# XBee-Regulated-v14.net
KiCad netlist of a schematic drawn in EAGLE
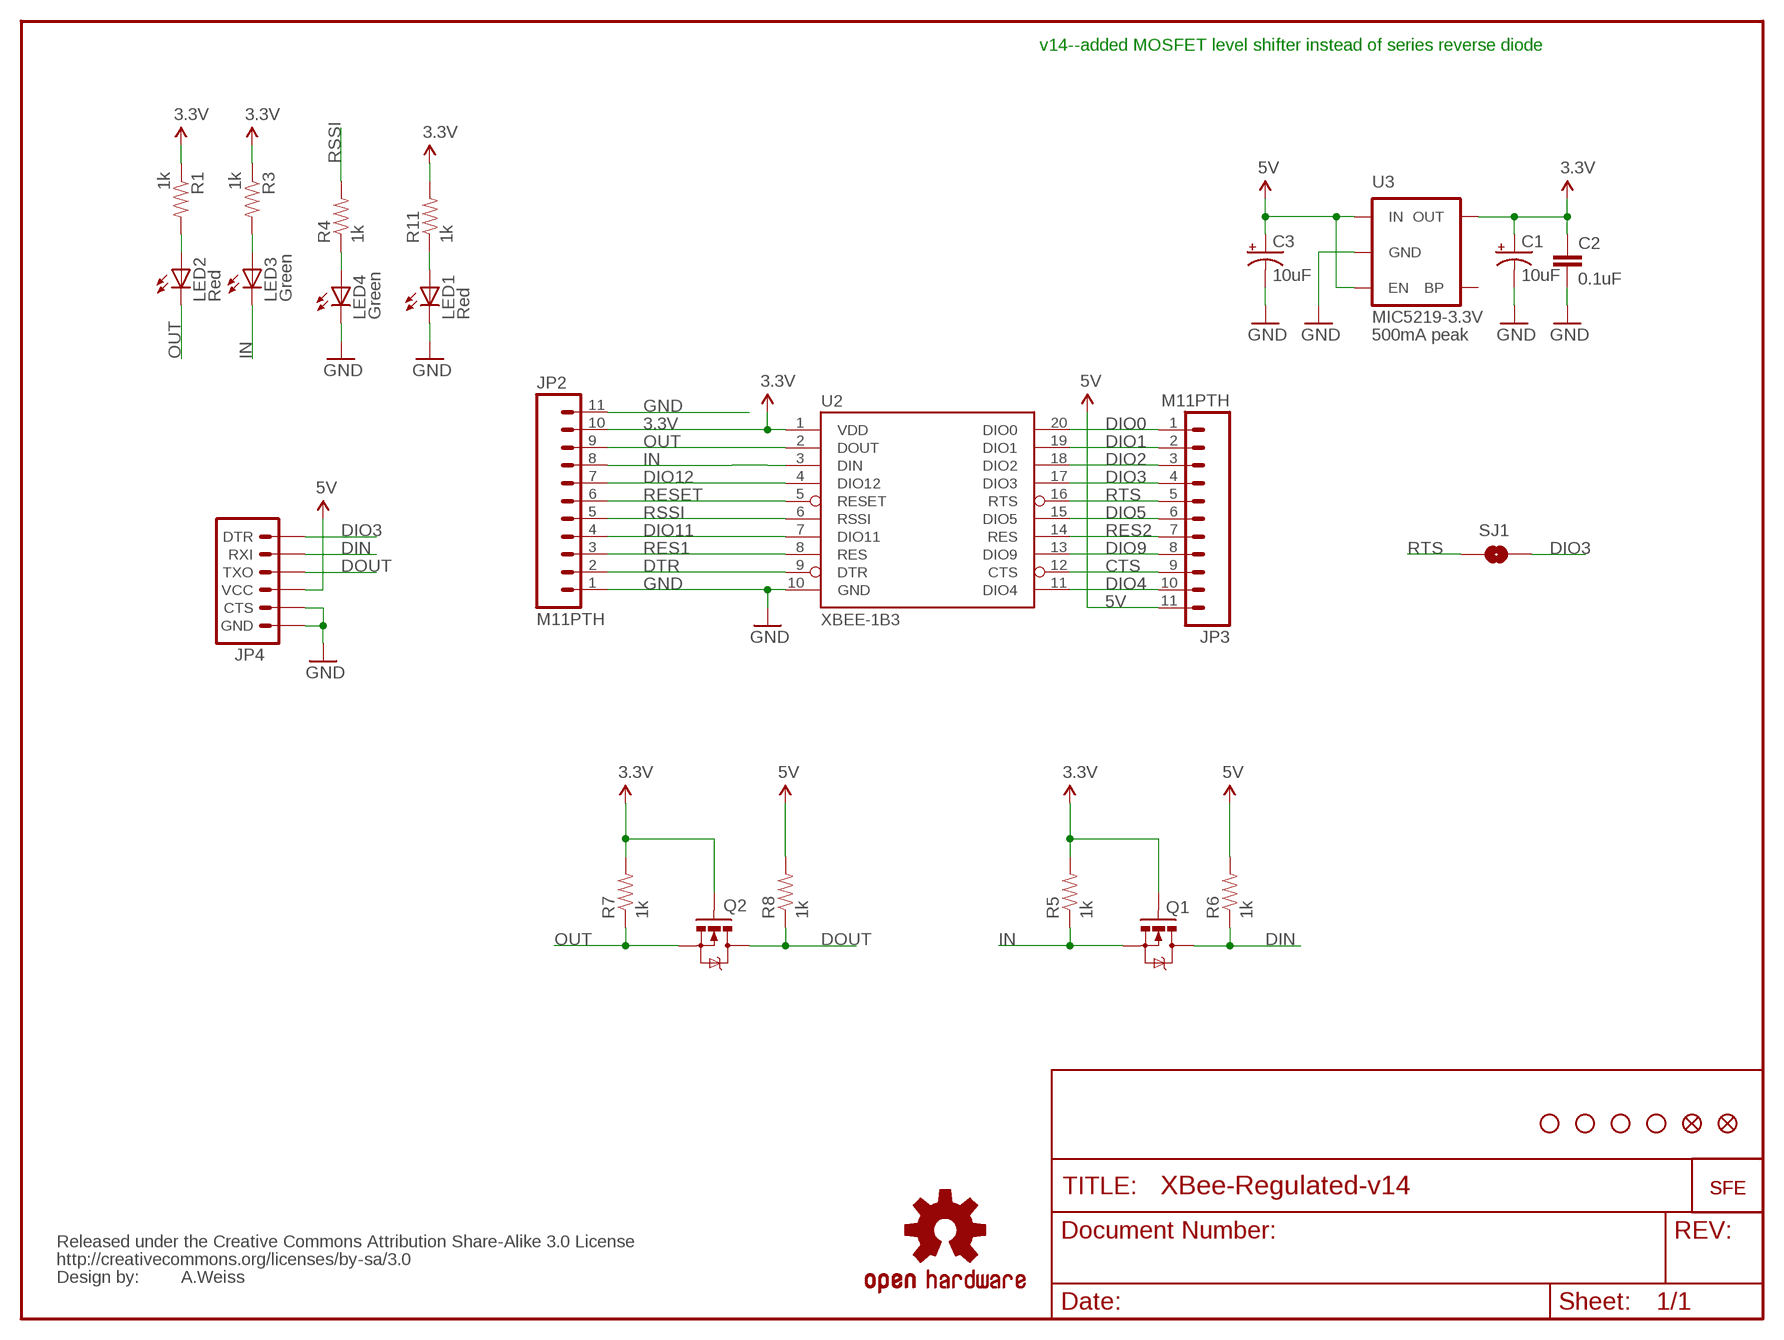
[diagram p0: schematic, sheet 1]

(export (version "E")
  (design (tool "Eeschema 10.0.6"))
  (components
    (comp (ref "C1")
      (value "10uF")
      (footprint "eagle-import:EIA3216")
      (libsource (lib "eagle-import") (part "CAP_POL1206"))
    )
    (comp (ref "C2")
      (value "0.1uF")
      (footprint "eagle-import:0402-CAP")
      (libsource (lib "eagle-import") (part "CAP0402-CAP"))
    )
    (comp (ref "C3")
      (value "10uF")
      (footprint "eagle-import:EIA3216")
      (libsource (lib "eagle-import") (part "CAP_POL1206"))
    )
    (comp (ref "JP2")
      (value "M11PTH")
      (footprint "eagle-import:1X11")
      (libsource (lib "eagle-import") (part "M11PTH"))
    )
    (comp (ref "JP3")
      (value "M11PTH")
      (footprint "eagle-import:1X11")
      (libsource (lib "eagle-import") (part "M11PTH"))
    )
    (comp (ref "JP4")
      (value "ARDUINO_SERIAL_PROGRAMPTH")
      (footprint "eagle-import:1X06")
      (libsource (lib "eagle-import") (part "ARDUINO_SERIAL_PROGRAMPTH"))
    )
    (comp (ref "LED1")
      (value "Red")
      (footprint "eagle-import:LED-0603")
      (libsource (lib "eagle-import") (part "LED0603"))
    )
    (comp (ref "LED2")
      (value "Red")
      (footprint "eagle-import:LED-0603")
      (libsource (lib "eagle-import") (part "LED0603"))
    )
    (comp (ref "LED3")
      (value "Green")
      (footprint "eagle-import:LED-0603")
      (libsource (lib "eagle-import") (part "LED0603"))
    )
    (comp (ref "LED4")
      (value "Green")
      (footprint "eagle-import:LED-0603")
      (libsource (lib "eagle-import") (part "LED0603"))
    )
    (comp (ref "Q1")
      (value "MOSFET-NCHANNELSMD")
      (footprint "eagle-import:SOT23-3")
      (libsource (lib "eagle-import") (part "MOSFET-NCHANNELSMD"))
    )
    (comp (ref "Q2")
      (value "MOSFET-NCHANNELSMD")
      (footprint "eagle-import:SOT23-3")
      (libsource (lib "eagle-import") (part "MOSFET-NCHANNELSMD"))
    )
    (comp (ref "R1")
      (value "1k")
      (footprint "eagle-import:0402-RES")
      (libsource (lib "eagle-import") (part "RESISTOR0402-RES"))
    )
    (comp (ref "R3")
      (value "1k")
      (footprint "eagle-import:0402-RES")
      (libsource (lib "eagle-import") (part "RESISTOR0402-RES"))
    )
    (comp (ref "R4")
      (value "1k")
      (footprint "eagle-import:0402-RES")
      (libsource (lib "eagle-import") (part "RESISTOR0402-RES"))
    )
    (comp (ref "R5")
      (value "1k")
      (footprint "eagle-import:0402-RES")
      (libsource (lib "eagle-import") (part "RESISTOR0402-RES"))
    )
    (comp (ref "R6")
      (value "1k")
      (footprint "eagle-import:0402-RES")
      (libsource (lib "eagle-import") (part "RESISTOR0402-RES"))
    )
    (comp (ref "R7")
      (value "1k")
      (footprint "eagle-import:0402-RES")
      (libsource (lib "eagle-import") (part "RESISTOR0402-RES"))
    )
    (comp (ref "R8")
      (value "1k")
      (footprint "eagle-import:0402-RES")
      (libsource (lib "eagle-import") (part "RESISTOR0402-RES"))
    )
    (comp (ref "R11")
      (value "1k")
      (footprint "eagle-import:0402-RES")
      (libsource (lib "eagle-import") (part "RESISTOR0402-RES"))
    )
    (comp (ref "SJ1")
      (value "SOLDERJUMPERNO")
      (footprint "eagle-import:SJ_2S-NO")
      (libsource (lib "eagle-import") (part "SOLDERJUMPERNO"))
    )
    (comp (ref "U$1")
      (value "LOGO-SFESK")
      (footprint "eagle-import:SFE-LOGO-FLAME")
      (libsource (lib "eagle-import") (part "LOGO-SFESK"))
    )
    (comp (ref "U$3")
      (value "OSHW-LOGOS")
      (footprint "eagle-import:OSHW-LOGO-S")
      (libsource (lib "eagle-import") (part "OSHW-LOGOS"))
    )
    (comp (ref "U$4")
      (value "LOGO-SFENEW")
      (footprint "eagle-import:SFE-NEW-WEBLOGO")
      (libsource (lib "eagle-import") (part "LOGO-SFENEW"))
    )
    (comp (ref "U$5")
      (value "STAND-OFF")
      (footprint "eagle-import:STAND-OFF")
      (libsource (lib "eagle-import") (part "STAND-OFF"))
    )
    (comp (ref "U$7")
      (value "FIDUCIAL1X2")
      (footprint "eagle-import:FIDUCIAL-1X2")
      (libsource (lib "eagle-import") (part "FIDUCIAL1X2"))
    )
    (comp (ref "U$8")
      (value "CREATIVE_COMMONS")
      (footprint "eagle-import:CREATIVE_COMMONS")
      (libsource (lib "eagle-import") (part "CREATIVE_COMMONS"))
    )
    (comp (ref "U$9")
      (value "STAND-OFF")
      (footprint "eagle-import:STAND-OFF")
      (libsource (lib "eagle-import") (part "STAND-OFF"))
    )
    (comp (ref "U$10")
      (value "STAND-OFF")
      (footprint "eagle-import:STAND-OFF")
      (libsource (lib "eagle-import") (part "STAND-OFF"))
    )
    (comp (ref "U$11")
      (value "STAND-OFF")
      (footprint "eagle-import:STAND-OFF")
      (libsource (lib "eagle-import") (part "STAND-OFF"))
    )
    (comp (ref "U$16")
      (value "FIDUCIAL1X2")
      (footprint "eagle-import:FIDUCIAL-1X2")
      (libsource (lib "eagle-import") (part "FIDUCIAL1X2"))
    )
    (comp (ref "U2")
      (value "XBEE-1B3")
      (footprint "eagle-import:XBEE-SMD")
      (libsource (lib "eagle-import") (part "XBEE-1B3"))
    )
    (comp (ref "U3")
      (value "V_REG_LDOSMD")
      (footprint "eagle-import:SOT23-5")
      (libsource (lib "eagle-import") (part "V_REG_LDOSMD"))
    )
  )
  (nets
    (net (code "1") (name "/CTS") (class "Default")
      (node (ref "JP3") (pin "9") (pinfunction "9_9") (pintype "passive"))
      (node (ref "U2") (pin "12") (pinfunction "CTS_12") (pintype "output"))
    )
    (net (code "2") (name "/DIN") (class "Default")
      (node (ref "JP4") (pin "2") (pinfunction "RXI_2") (pintype "passive"))
      (node (ref "Q1") (pin "3") (pinfunction "D_3") (pintype "passive"))
      (node (ref "R6") (pin "1") (pinfunction "1_1") (pintype "passive"))
    )
    (net (code "3") (name "/DIO0") (class "Default")
      (node (ref "JP3") (pin "1") (pinfunction "1_1") (pintype "passive"))
      (node (ref "U2") (pin "20") (pinfunction "DIO0_20") (pintype "bidirectional"))
    )
    (net (code "4") (name "/DIO1") (class "Default")
      (node (ref "JP3") (pin "2") (pinfunction "2_2") (pintype "passive"))
      (node (ref "U2") (pin "19") (pinfunction "DIO1_19") (pintype "bidirectional"))
    )
    (net (code "5") (name "/DIO2") (class "Default")
      (node (ref "JP3") (pin "3") (pinfunction "3_3") (pintype "passive"))
      (node (ref "U2") (pin "18") (pinfunction "DIO2_18") (pintype "bidirectional"))
    )
    (net (code "6") (name "/DIO3") (class "Default")
      (node (ref "JP3") (pin "4") (pinfunction "4_4") (pintype "passive"))
      (node (ref "JP4") (pin "1") (pinfunction "DTR_1") (pintype "passive"))
      (node (ref "SJ1") (pin "2") (pinfunction "2_2") (pintype "passive"))
      (node (ref "U2") (pin "17") (pinfunction "DIO3_17") (pintype "bidirectional"))
    )
    (net (code "7") (name "/DIO4") (class "Default")
      (node (ref "JP3") (pin "10") (pinfunction "10_10") (pintype "passive"))
      (node (ref "U2") (pin "11") (pinfunction "DIO4_11") (pintype "bidirectional"))
    )
    (net (code "8") (name "/DIO5") (class "Default")
      (node (ref "JP3") (pin "6") (pinfunction "6_6") (pintype "passive"))
      (node (ref "U2") (pin "15") (pinfunction "DIO5_15") (pintype "bidirectional"))
    )
    (net (code "9") (name "/DIO9") (class "Default")
      (node (ref "JP3") (pin "8") (pinfunction "8_8") (pintype "passive"))
      (node (ref "U2") (pin "13") (pinfunction "DIO9_13") (pintype "bidirectional"))
    )
    (net (code "10") (name "/DIO11") (class "Default")
      (node (ref "JP2") (pin "4") (pinfunction "4_4") (pintype "passive"))
      (node (ref "U2") (pin "7") (pinfunction "DIO11_7") (pintype "bidirectional"))
    )
    (net (code "11") (name "/DIO12") (class "Default")
      (node (ref "JP2") (pin "7") (pinfunction "7_7") (pintype "passive"))
      (node (ref "U2") (pin "4") (pinfunction "DIO12_4") (pintype "bidirectional"))
    )
    (net (code "12") (name "/DOUT") (class "Default")
      (node (ref "JP4") (pin "3") (pinfunction "TXO_3") (pintype "passive"))
      (node (ref "Q2") (pin "3") (pinfunction "D_3") (pintype "passive"))
      (node (ref "R8") (pin "1") (pinfunction "1_1") (pintype "passive"))
    )
    (net (code "13") (name "/DTR") (class "Default")
      (node (ref "JP2") (pin "2") (pinfunction "2_2") (pintype "passive"))
      (node (ref "U2") (pin "9") (pinfunction "DTR_9") (pintype "bidirectional"))
    )
    (net (code "14") (name "/IN") (class "Default")
      (node (ref "JP2") (pin "8") (pinfunction "8_8") (pintype "passive"))
      (node (ref "LED3") (pin "C") (pinfunction "C_C") (pintype "passive"))
      (node (ref "Q1") (pin "2") (pinfunction "S_2") (pintype "passive"))
      (node (ref "R5") (pin "1") (pinfunction "1_1") (pintype "passive"))
      (node (ref "U2") (pin "3") (pinfunction "DIN_3") (pintype "input"))
    )
    (net (code "15") (name "/OUT") (class "Default")
      (node (ref "JP2") (pin "9") (pinfunction "9_9") (pintype "passive"))
      (node (ref "LED2") (pin "C") (pinfunction "C_C") (pintype "passive"))
      (node (ref "Q2") (pin "2") (pinfunction "S_2") (pintype "passive"))
      (node (ref "R7") (pin "1") (pinfunction "1_1") (pintype "passive"))
      (node (ref "U2") (pin "2") (pinfunction "DOUT_2") (pintype "output"))
    )
    (net (code "16") (name "/RES1") (class "Default")
      (node (ref "JP2") (pin "3") (pinfunction "3_3") (pintype "passive"))
      (node (ref "U2") (pin "8") (pinfunction "RES_8") (pintype "bidirectional"))
    )
    (net (code "17") (name "/RES2") (class "Default")
      (node (ref "JP3") (pin "7") (pinfunction "7_7") (pintype "passive"))
      (node (ref "U2") (pin "14") (pinfunction "RES_14") (pintype "bidirectional"))
    )
    (net (code "18") (name "/RESET") (class "Default")
      (node (ref "JP2") (pin "6") (pinfunction "6_6") (pintype "passive"))
      (node (ref "U2") (pin "5") (pinfunction "RESET_5") (pintype "input"))
    )
    (net (code "19") (name "/RSSI") (class "Default")
      (node (ref "JP2") (pin "5") (pinfunction "5_5") (pintype "passive"))
      (node (ref "R4") (pin "2") (pinfunction "2_2") (pintype "passive"))
      (node (ref "U2") (pin "6") (pinfunction "RSSI_6") (pintype "bidirectional"))
    )
    (net (code "20") (name "/RTS") (class "Default")
      (node (ref "JP3") (pin "5") (pinfunction "5_5") (pintype "passive"))
      (node (ref "SJ1") (pin "1") (pinfunction "1_1") (pintype "passive"))
      (node (ref "U2") (pin "16") (pinfunction "RTS_16") (pintype "input"))
    )
    (net (code "21") (name "3.3V") (class "Default")
      (node (ref "C1") (pin "A") (pinfunction "+_A") (pintype "passive"))
      (node (ref "C2") (pin "1") (pinfunction "1_1") (pintype "passive"))
      (node (ref "JP2") (pin "10") (pinfunction "10_10") (pintype "passive"))
      (node (ref "Q1") (pin "1") (pinfunction "G_1") (pintype "passive"))
      (node (ref "Q2") (pin "1") (pinfunction "G_1") (pintype "passive"))
      (node (ref "R1") (pin "1") (pinfunction "1_1") (pintype "passive"))
      (node (ref "R11") (pin "2") (pinfunction "2_2") (pintype "passive"))
      (node (ref "R3") (pin "1") (pinfunction "1_1") (pintype "passive"))
      (node (ref "R5") (pin "2") (pinfunction "2_2") (pintype "passive"))
      (node (ref "R7") (pin "2") (pinfunction "2_2") (pintype "passive"))
      (node (ref "U2") (pin "1") (pinfunction "VDD_1") (pintype "power_in"))
      (node (ref "U3") (pin "5") (pinfunction "OUT_5") (pintype "passive"))
    )
    (net (code "22") (name "5V") (class "Default")
      (node (ref "C3") (pin "A") (pinfunction "+_A") (pintype "passive"))
      (node (ref "JP3") (pin "11") (pinfunction "11_11") (pintype "passive"))
      (node (ref "JP4") (pin "4") (pinfunction "VCC_4") (pintype "passive"))
      (node (ref "R6") (pin "2") (pinfunction "2_2") (pintype "passive"))
      (node (ref "R8") (pin "2") (pinfunction "2_2") (pintype "passive"))
      (node (ref "U3") (pin "1") (pinfunction "IN_1") (pintype "input"))
      (node (ref "U3") (pin "3") (pinfunction "EN_3") (pintype "input"))
    )
    (net (code "23") (name "GND") (class "Default")
      (node (ref "C1") (pin "C") (pinfunction "-_C") (pintype "passive"))
      (node (ref "C2") (pin "2") (pinfunction "2_2") (pintype "passive"))
      (node (ref "C3") (pin "C") (pinfunction "-_C") (pintype "passive"))
      (node (ref "JP2") (pin "1") (pinfunction "1_1") (pintype "passive"))
      (node (ref "JP2") (pin "11") (pinfunction "11_11") (pintype "passive"))
      (node (ref "JP4") (pin "5") (pinfunction "CTS_5") (pintype "passive"))
      (node (ref "JP4") (pin "6") (pinfunction "GND_6") (pintype "passive"))
      (node (ref "LED1") (pin "C") (pinfunction "C_C") (pintype "passive"))
      (node (ref "LED4") (pin "C") (pinfunction "C_C") (pintype "passive"))
      (node (ref "U2") (pin "10") (pinfunction "GND_10") (pintype "power_in"))
      (node (ref "U3") (pin "2") (pinfunction "GND_2") (pintype "input"))
    )
    (net (code "24") (name "Net-(LED1-PadA)") (class "Default")
      (node (ref "LED1") (pin "A") (pinfunction "A_A") (pintype "passive"))
      (node (ref "R11") (pin "1") (pinfunction "1_1") (pintype "passive"))
    )
    (net (code "25") (name "Net-(LED2-PadA)") (class "Default")
      (node (ref "LED2") (pin "A") (pinfunction "A_A") (pintype "passive"))
      (node (ref "R1") (pin "2") (pinfunction "2_2") (pintype "passive"))
    )
    (net (code "26") (name "Net-(LED3-PadA)") (class "Default")
      (node (ref "LED3") (pin "A") (pinfunction "A_A") (pintype "passive"))
      (node (ref "R3") (pin "2") (pinfunction "2_2") (pintype "passive"))
    )
    (net (code "27") (name "Net-(LED4-PadA)") (class "Default")
      (node (ref "LED4") (pin "A") (pinfunction "A_A") (pintype "passive"))
      (node (ref "R4") (pin "1") (pinfunction "1_1") (pintype "passive"))
    )
    (net (code "28") (name "unconnected-(U3-BP-Pad4)") (class "Default")
      (node (ref "U3") (pin "4") (pinfunction "BP_4") (pintype "input"))
    )
  )
)
